# finalboardsch.net
KiCad netlist of a schematic drawn in EAGLE
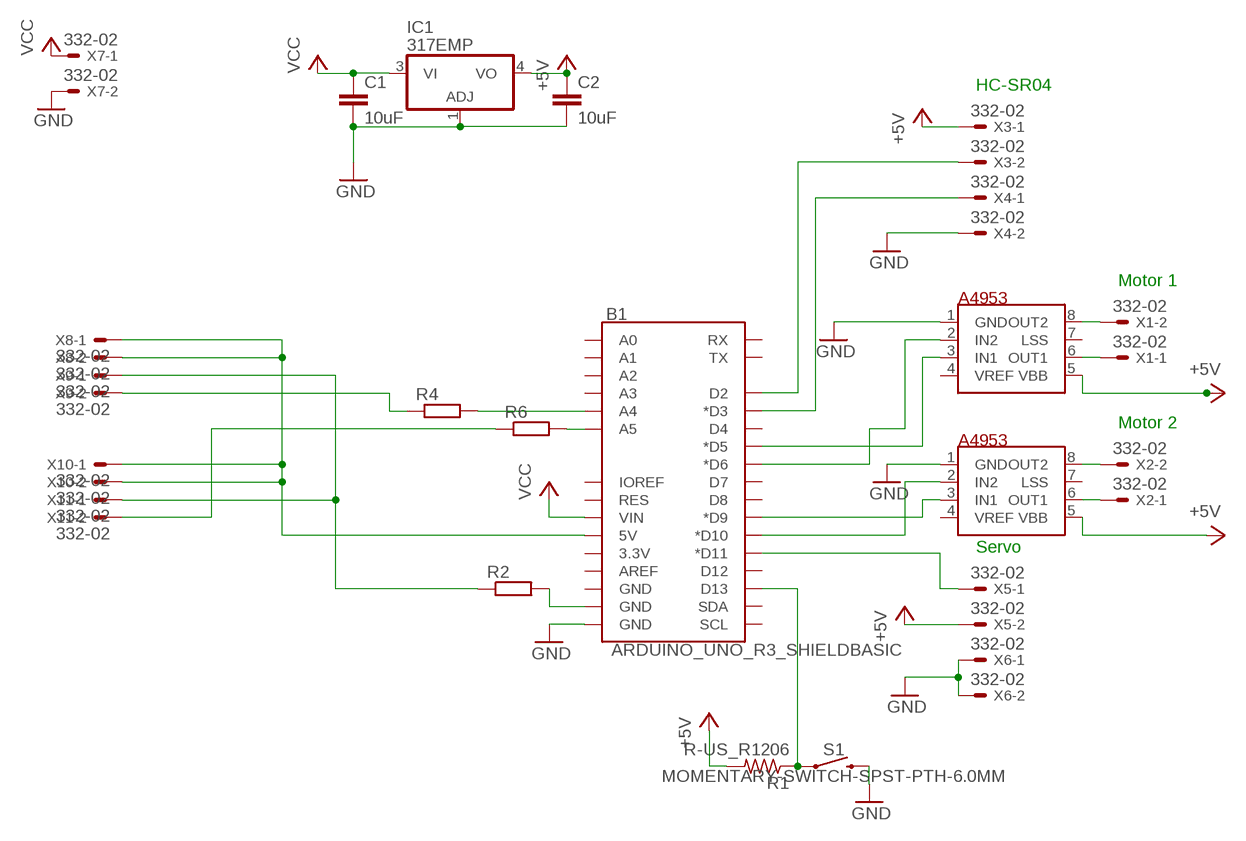
[diagram p0: schematic, sheet 1]

(export (version "E")
  (design (tool "Eeschema 10.0.6"))
  (components
    (comp (ref "A1")
      (value "A4953")
      (footprint "eagle-import:SO08")
      (libsource (lib "eagle-import") (part "A4953"))
    )
    (comp (ref "A2")
      (value "A4953")
      (footprint "eagle-import:SO08")
      (libsource (lib "eagle-import") (part "A4953"))
    )
    (comp (ref "B1")
      (value "ARDUINO_UNO_R3_SHIELDBASIC")
      (footprint "eagle-import:UNO_R3_SHIELD")
      (libsource (lib "eagle-import") (part "ARDUINO_UNO_R3_SHIELDBASIC"))
    )
    (comp (ref "C1")
      (value "10uF")
      (footprint "eagle-import:1206")
      (libsource (lib "eagle-import") (part "10UF-1206-6.3V-20%"))
    )
    (comp (ref "C2")
      (value "10uF")
      (footprint "eagle-import:1206")
      (libsource (lib "eagle-import") (part "10UF-1206-6.3V-20%"))
    )
    (comp (ref "IC1")
      (value "317EMP")
      (footprint "eagle-import:SOT223")
      (libsource (lib "eagle-import") (part "317EMP"))
    )
    (comp (ref "R1")
      (value "R-US_R1206")
      (footprint "eagle-import:R1206")
      (libsource (lib "eagle-import") (part "R-US_R1206"))
    )
    (comp (ref "R2")
      (value "RR1206")
      (footprint "eagle-import:R1206")
      (libsource (lib "eagle-import") (part "RR1206"))
    )
    (comp (ref "R4")
      (value "RR1206")
      (footprint "eagle-import:R1206")
      (libsource (lib "eagle-import") (part "RR1206"))
    )
    (comp (ref "R6")
      (value "RR1206")
      (footprint "eagle-import:R1206")
      (libsource (lib "eagle-import") (part "RR1206"))
    )
    (comp (ref "S1")
      (value "MOMENTARY-SWITCH-SPST-PTH-6.0MM")
      (footprint "eagle-import:TACTILE_SWITCH_PTH_6.0MM")
      (libsource (lib "eagle-import") (part "MOMENTARY-SWITCH-SPST-PTH-6.0MM"))
    )
    (comp (ref "X1")
      (value "332-02")
      (footprint "eagle-import:332-02")
      (libsource (lib "eagle-import") (part "332-02"))
    )
    (comp (ref "X2")
      (value "332-02")
      (footprint "eagle-import:332-02")
      (libsource (lib "eagle-import") (part "332-02"))
    )
    (comp (ref "X3")
      (value "332-02")
      (footprint "eagle-import:332-02")
      (libsource (lib "eagle-import") (part "332-02"))
    )
    (comp (ref "X4")
      (value "332-02")
      (footprint "eagle-import:332-02")
      (libsource (lib "eagle-import") (part "332-02"))
    )
    (comp (ref "X5")
      (value "332-02")
      (footprint "eagle-import:332-02")
      (libsource (lib "eagle-import") (part "332-02"))
    )
    (comp (ref "X6")
      (value "332-02")
      (footprint "eagle-import:332-02")
      (libsource (lib "eagle-import") (part "332-02"))
    )
    (comp (ref "X7")
      (value "332-02")
      (footprint "eagle-import:332-02")
      (libsource (lib "eagle-import") (part "332-02"))
    )
    (comp (ref "X8")
      (value "332-02")
      (footprint "eagle-import:332-02")
      (libsource (lib "eagle-import") (part "332-02"))
    )
    (comp (ref "X9")
      (value "332-02")
      (footprint "eagle-import:332-02")
      (libsource (lib "eagle-import") (part "332-02"))
    )
    (comp (ref "X10")
      (value "332-02")
      (footprint "eagle-import:332-02")
      (libsource (lib "eagle-import") (part "332-02"))
    )
    (comp (ref "X11")
      (value "332-02")
      (footprint "eagle-import:332-02")
      (libsource (lib "eagle-import") (part "332-02"))
    )
  )
  (nets
    (net (code "1") (name "+5V") (class "Default")
      (node (ref "A1") (pin "5") (pinfunction "VBB_5") (pintype "power_in"))
      (node (ref "A2") (pin "5") (pinfunction "VBB_5") (pintype "power_in"))
      (node (ref "C2") (pin "1") (pinfunction "1_1") (pintype "passive"))
      (node (ref "IC1") (pin "4") (pinfunction "VO_4") (pintype "passive"))
      (node (ref "R1") (pin "2") (pinfunction "2_2") (pintype "passive"))
      (node (ref "X3") (pin "1") (pinfunction "S_1") (pintype "passive"))
      (node (ref "X5") (pin "2") (pinfunction "S_2") (pintype "passive"))
    )
    (net (code "2") (name "GND") (class "Default")
      (node (ref "A1") (pin "1") (pinfunction "GND_1") (pintype "power_in"))
      (node (ref "A2") (pin "1") (pinfunction "GND_1") (pintype "power_in"))
      (node (ref "B1") (pin "GND@0") (pinfunction "GND_GND@0") (pintype "bidirectional"))
      (node (ref "C1") (pin "2") (pinfunction "2_2") (pintype "passive"))
      (node (ref "C2") (pin "2") (pinfunction "2_2") (pintype "passive"))
      (node (ref "IC1") (pin "1") (pinfunction "ADJ_1") (pintype "input"))
      (node (ref "S1") (pin "3") (pinfunction "2_3") (pintype "passive"))
      (node (ref "X4") (pin "2") (pinfunction "S_2") (pintype "passive"))
      (node (ref "X6") (pin "1") (pinfunction "S_1") (pintype "passive"))
      (node (ref "X6") (pin "2") (pinfunction "S_2") (pintype "passive"))
      (node (ref "X7") (pin "2") (pinfunction "S_2") (pintype "passive"))
    )
    (net (code "3") (name "Net-(A1-IN1)") (class "Default")
      (node (ref "A1") (pin "3") (pinfunction "IN1_3") (pintype "input"))
      (node (ref "B1") (pin "D5") (pinfunction "*D5_D5") (pintype "bidirectional"))
    )
    (net (code "4") (name "Net-(A1-IN2)") (class "Default")
      (node (ref "A1") (pin "2") (pinfunction "IN2_2") (pintype "input"))
      (node (ref "B1") (pin "D6") (pinfunction "*D6_D6") (pintype "bidirectional"))
    )
    (net (code "5") (name "Net-(A1-OUT1)") (class "Default")
      (node (ref "A1") (pin "6") (pinfunction "OUT1_6") (pintype "output"))
      (node (ref "X1") (pin "1") (pinfunction "S_1") (pintype "passive"))
    )
    (net (code "6") (name "Net-(A1-OUT2)") (class "Default")
      (node (ref "A1") (pin "8") (pinfunction "OUT2_8") (pintype "output"))
      (node (ref "X1") (pin "2") (pinfunction "S_2") (pintype "passive"))
    )
    (net (code "7") (name "Net-(A2-IN1)") (class "Default")
      (node (ref "A2") (pin "3") (pinfunction "IN1_3") (pintype "input"))
      (node (ref "B1") (pin "D9") (pinfunction "*D9_D9") (pintype "bidirectional"))
    )
    (net (code "8") (name "Net-(A2-IN2)") (class "Default")
      (node (ref "A2") (pin "2") (pinfunction "IN2_2") (pintype "input"))
      (node (ref "B1") (pin "D10") (pinfunction "*D10_D10") (pintype "bidirectional"))
    )
    (net (code "9") (name "Net-(A2-OUT1)") (class "Default")
      (node (ref "A2") (pin "6") (pinfunction "OUT1_6") (pintype "output"))
      (node (ref "X2") (pin "1") (pinfunction "S_1") (pintype "passive"))
    )
    (net (code "10") (name "Net-(A2-OUT2)") (class "Default")
      (node (ref "A2") (pin "8") (pinfunction "OUT2_8") (pintype "output"))
      (node (ref "X2") (pin "2") (pinfunction "S_2") (pintype "passive"))
    )
    (net (code "11") (name "Net-(B1-*D3)") (class "Default")
      (node (ref "B1") (pin "D3") (pinfunction "*D3_D3") (pintype "bidirectional"))
      (node (ref "X4") (pin "1") (pinfunction "S_1") (pintype "passive"))
    )
    (net (code "12") (name "Net-(B1-*D11)") (class "Default")
      (node (ref "B1") (pin "D11") (pinfunction "*D11_D11") (pintype "bidirectional"))
      (node (ref "X5") (pin "1") (pinfunction "S_1") (pintype "passive"))
    )
    (net (code "13") (name "Net-(B1-GND-PadGND@1)") (class "Default")
      (node (ref "B1") (pin "GND@1") (pinfunction "GND_GND@1") (pintype "bidirectional"))
      (node (ref "R2") (pin "2") (pinfunction "2_2") (pintype "passive"))
    )
    (net (code "14") (name "Net-(B1-PadA4)") (class "Default")
      (node (ref "B1") (pin "A4") (pinfunction "A4_A4") (pintype "bidirectional"))
      (node (ref "R4") (pin "2") (pinfunction "2_2") (pintype "passive"))
    )
    (net (code "15") (name "Net-(B1-PadA5)") (class "Default")
      (node (ref "B1") (pin "A5") (pinfunction "A5_A5") (pintype "bidirectional"))
      (node (ref "R6") (pin "2") (pinfunction "2_2") (pintype "passive"))
    )
    (net (code "16") (name "Net-(B1-PadD13)") (class "Default")
      (node (ref "B1") (pin "D13") (pinfunction "D13_D13") (pintype "bidirectional"))
      (node (ref "R1") (pin "1") (pinfunction "1_1") (pintype "passive"))
      (node (ref "S1") (pin "1") (pinfunction "1_1") (pintype "passive"))
    )
    (net (code "17") (name "Net-(X3B-S)") (class "Default")
      (node (ref "B1") (pin "D2") (pinfunction "D2_D2") (pintype "bidirectional"))
      (node (ref "X3") (pin "2") (pinfunction "S_2") (pintype "passive"))
    )
    (net (code "18") (name "Net-(X9B-S)") (class "Default")
      (node (ref "R4") (pin "1") (pinfunction "1_1") (pintype "passive"))
      (node (ref "X9") (pin "2") (pinfunction "S_2") (pintype "passive"))
    )
    (net (code "19") (name "Net-(X10A-S)") (class "Default")
      (node (ref "B1") (pin "5V") (pinfunction "5V_5V") (pintype "bidirectional"))
      (node (ref "X10") (pin "1") (pinfunction "S_1") (pintype "passive"))
      (node (ref "X10") (pin "2") (pinfunction "S_2") (pintype "passive"))
      (node (ref "X8") (pin "1") (pinfunction "S_1") (pintype "passive"))
      (node (ref "X8") (pin "2") (pinfunction "S_2") (pintype "passive"))
    )
    (net (code "20") (name "Net-(X11A-S)") (class "Default")
      (node (ref "R2") (pin "1") (pinfunction "1_1") (pintype "passive"))
      (node (ref "X11") (pin "1") (pinfunction "S_1") (pintype "passive"))
      (node (ref "X9") (pin "1") (pinfunction "S_1") (pintype "passive"))
    )
    (net (code "21") (name "Net-(X11B-S)") (class "Default")
      (node (ref "R6") (pin "1") (pinfunction "1_1") (pintype "passive"))
      (node (ref "X11") (pin "2") (pinfunction "S_2") (pintype "passive"))
    )
    (net (code "22") (name "VCC") (class "Default")
      (node (ref "B1") (pin "VIN") (pinfunction "VIN_VIN") (pintype "bidirectional"))
      (node (ref "C1") (pin "1") (pinfunction "1_1") (pintype "passive"))
      (node (ref "IC1") (pin "3") (pinfunction "VI_3") (pintype "input"))
      (node (ref "X7") (pin "1") (pinfunction "S_1") (pintype "passive"))
    )
    (net (code "23") (name "unconnected-(A1-LSS-Pad7)") (class "Default")
      (node (ref "A1") (pin "7") (pinfunction "LSS_7") (pintype "input"))
    )
    (net (code "24") (name "unconnected-(A1-VREF-Pad4)") (class "Default")
      (node (ref "A1") (pin "4") (pinfunction "VREF_4") (pintype "input"))
    )
    (net (code "25") (name "unconnected-(A2-LSS-Pad7)") (class "Default")
      (node (ref "A2") (pin "7") (pinfunction "LSS_7") (pintype "input"))
    )
    (net (code "26") (name "unconnected-(A2-VREF-Pad4)") (class "Default")
      (node (ref "A2") (pin "4") (pinfunction "VREF_4") (pintype "input"))
    )
    (net (code "27") (name "unconnected-(B1-GND-PadGND@2)") (class "Default")
      (node (ref "B1") (pin "GND@2") (pinfunction "GND_GND@2") (pintype "bidirectional"))
    )
    (net (code "28") (name "unconnected-(B1-Pad3.3V)") (class "Default")
      (node (ref "B1") (pin "3.3V") (pinfunction "3.3V_3.3V") (pintype "bidirectional"))
    )
    (net (code "29") (name "unconnected-(B1-PadA0)") (class "Default")
      (node (ref "B1") (pin "A0") (pinfunction "A0_A0") (pintype "bidirectional"))
    )
    (net (code "30") (name "unconnected-(B1-PadA1)") (class "Default")
      (node (ref "B1") (pin "A1") (pinfunction "A1_A1") (pintype "bidirectional"))
    )
    (net (code "31") (name "unconnected-(B1-PadA2)") (class "Default")
      (node (ref "B1") (pin "A2") (pinfunction "A2_A2") (pintype "bidirectional"))
    )
    (net (code "32") (name "unconnected-(B1-PadA3)") (class "Default")
      (node (ref "B1") (pin "A3") (pinfunction "A3_A3") (pintype "bidirectional"))
    )
    (net (code "33") (name "unconnected-(B1-PadAREF)") (class "Default")
      (node (ref "B1") (pin "AREF") (pinfunction "AREF_AREF") (pintype "bidirectional"))
    )
    (net (code "34") (name "unconnected-(B1-PadD4)") (class "Default")
      (node (ref "B1") (pin "D4") (pinfunction "D4_D4") (pintype "bidirectional"))
    )
    (net (code "35") (name "unconnected-(B1-PadD7)") (class "Default")
      (node (ref "B1") (pin "D7") (pinfunction "D7_D7") (pintype "bidirectional"))
    )
    (net (code "36") (name "unconnected-(B1-PadD8)") (class "Default")
      (node (ref "B1") (pin "D8") (pinfunction "D8_D8") (pintype "bidirectional"))
    )
    (net (code "37") (name "unconnected-(B1-PadD12)") (class "Default")
      (node (ref "B1") (pin "D12") (pinfunction "D12_D12") (pintype "bidirectional"))
    )
    (net (code "38") (name "unconnected-(B1-PadIOREF)") (class "Default")
      (node (ref "B1") (pin "IOREF") (pinfunction "IOREF_IOREF") (pintype "bidirectional"))
    )
    (net (code "39") (name "unconnected-(B1-PadRES)") (class "Default")
      (node (ref "B1") (pin "RES") (pinfunction "RES_RES") (pintype "bidirectional"))
    )
    (net (code "40") (name "unconnected-(B1-PadRX)") (class "Default")
      (node (ref "B1") (pin "RX") (pinfunction "RX_RX") (pintype "bidirectional"))
    )
    (net (code "41") (name "unconnected-(B1-PadSCL)") (class "Default")
      (node (ref "B1") (pin "SCL") (pinfunction "SCL_SCL") (pintype "bidirectional"))
    )
    (net (code "42") (name "unconnected-(B1-PadSDA)") (class "Default")
      (node (ref "B1") (pin "SDA") (pinfunction "SDA_SDA") (pintype "bidirectional"))
    )
    (net (code "43") (name "unconnected-(B1-PadTX)") (class "Default")
      (node (ref "B1") (pin "TX") (pinfunction "TX_TX") (pintype "bidirectional"))
    )
  )
)
